# LiFePO4_Power.net
KiCad netlist of a schematic drawn in EAGLE
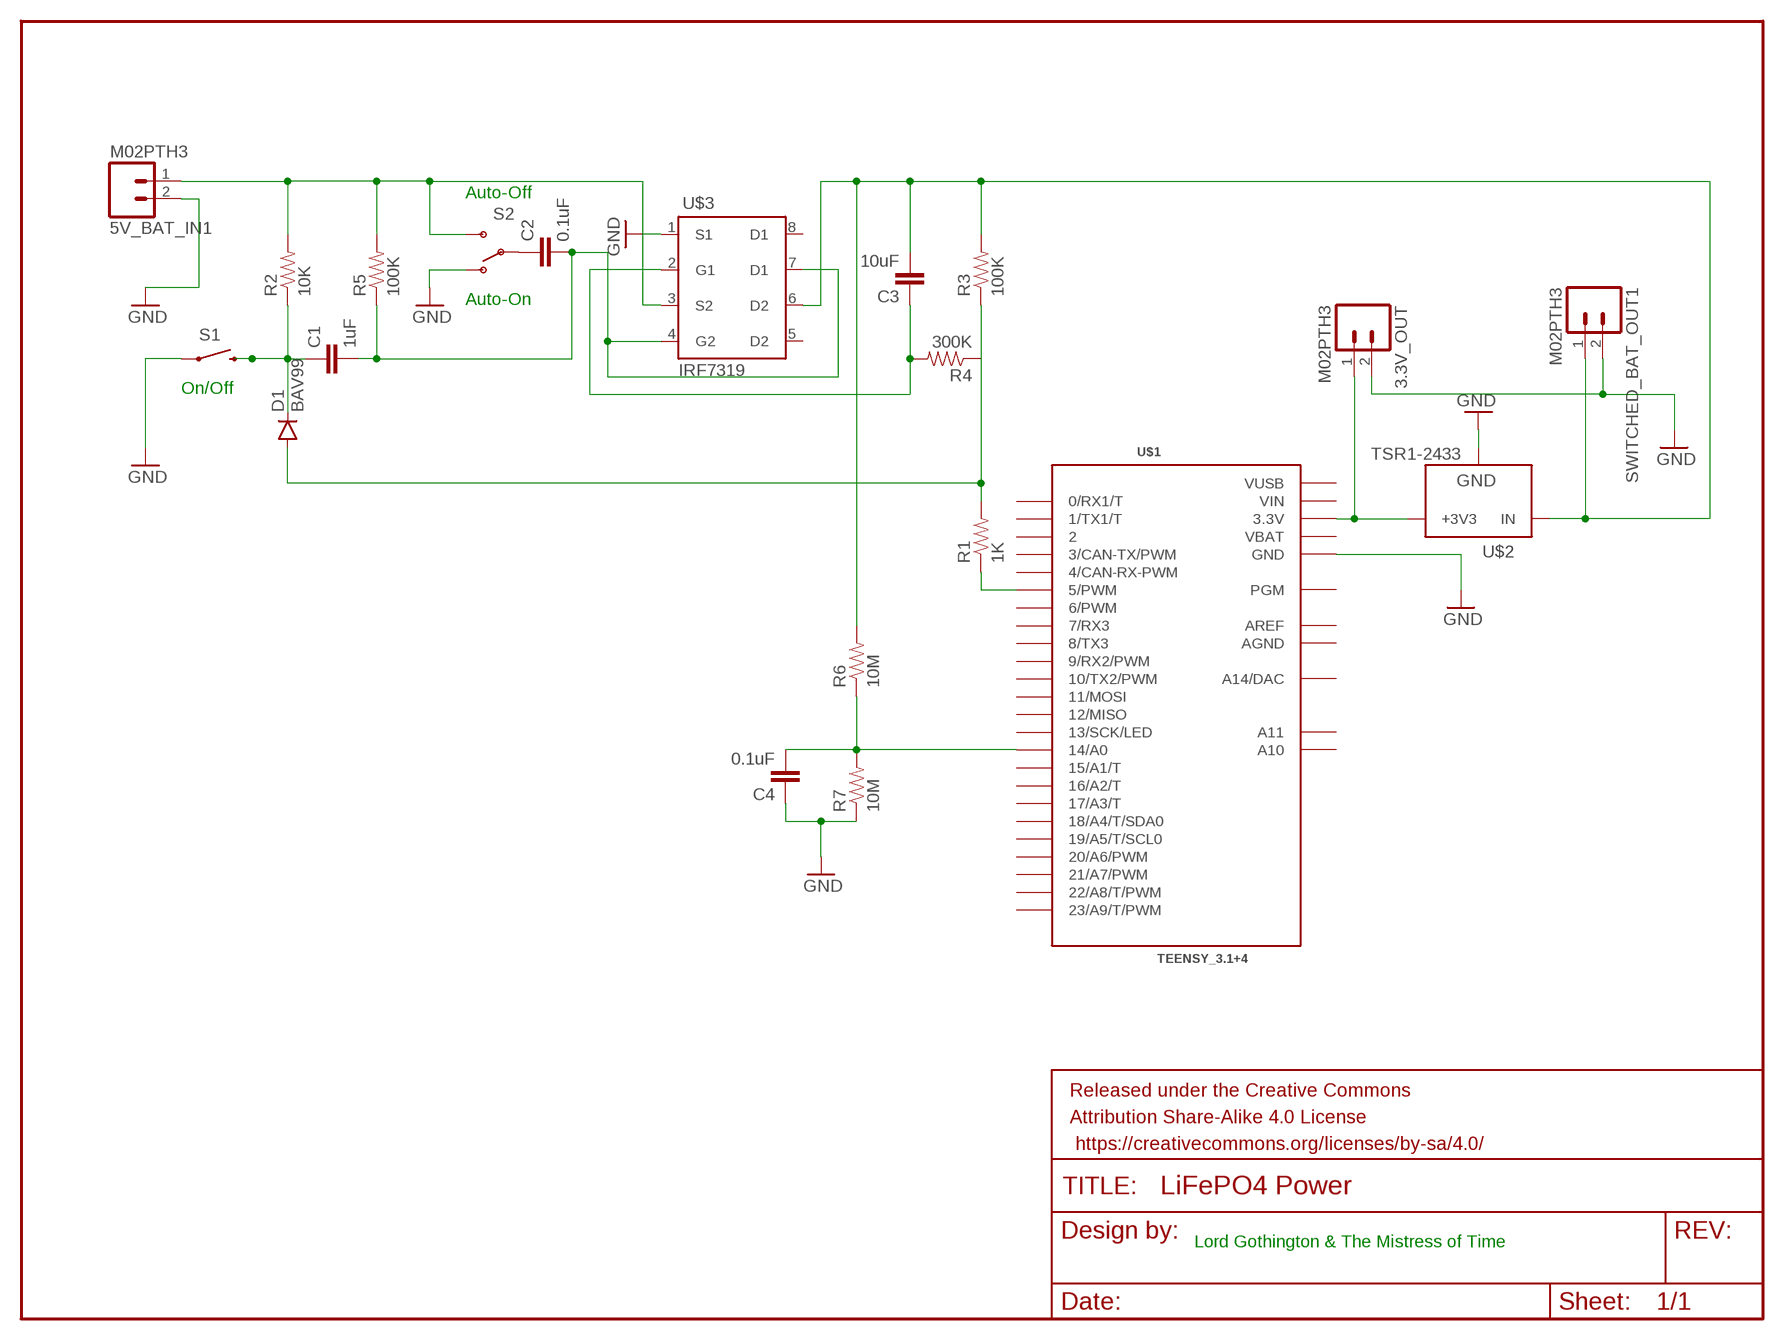
[diagram p0: schematic, sheet 1]

(export (version "E")
  (design (tool "Eeschema 10.0.6"))
  (components
    (comp (ref "3.3V_OUT")
      (value "M02PTH3")
      (footprint "eagle-import:1X02_LONGPADS")
      (libsource (lib "eagle-import") (part "M02PTH3"))
    )
    (comp (ref "5V_BAT_IN1")
      (value "M02PTH3")
      (footprint "eagle-import:1X02_LONGPADS")
      (libsource (lib "eagle-import") (part "M02PTH3"))
    )
    (comp (ref "C1")
      (value "1uF")
      (footprint "eagle-import:0805")
      (libsource (lib "eagle-import") (part "CAP0805"))
    )
    (comp (ref "C2")
      (value "0.1uF")
      (footprint "eagle-import:0805")
      (libsource (lib "eagle-import") (part "CAP0805"))
    )
    (comp (ref "C3")
      (value "10uF")
      (footprint "eagle-import:0805")
      (libsource (lib "eagle-import") (part "CAP0805"))
    )
    (comp (ref "C4")
      (value "0.1uF")
      (footprint "eagle-import:0805")
      (libsource (lib "eagle-import") (part "CAP0805"))
    )
    (comp (ref "D1")
      (value "BAV99")
      (footprint "eagle-import:SMA-DIODE")
      (libsource (lib "eagle-import") (part "DIODESMA"))
    )
    (comp (ref "FRAME1")
      (value "FRAME-LETTER")
      (footprint "eagle-import:CREATIVE_COMMONS")
      (libsource (lib "eagle-import") (part "FRAME-LETTER"))
    )
    (comp (ref "R1")
      (value "1K")
      (footprint "eagle-import:0805")
      (libsource (lib "eagle-import") (part "RESISTOR0805-RES"))
    )
    (comp (ref "R2")
      (value "10K")
      (footprint "eagle-import:0805")
      (libsource (lib "eagle-import") (part "RESISTOR0805-RES"))
    )
    (comp (ref "R3")
      (value "100K")
      (footprint "eagle-import:0805")
      (libsource (lib "eagle-import") (part "RESISTOR0805-RES"))
    )
    (comp (ref "R4")
      (value "300K")
      (footprint "eagle-import:0805")
      (libsource (lib "eagle-import") (part "RESISTOR0805-RES"))
    )
    (comp (ref "R5")
      (value "100K")
      (footprint "eagle-import:0805")
      (libsource (lib "eagle-import") (part "RESISTOR0805-RES"))
    )
    (comp (ref "R6")
      (value "10M")
      (footprint "eagle-import:0805")
      (libsource (lib "eagle-import") (part "RESISTOR0805-RES"))
    )
    (comp (ref "R7")
      (value "10M")
      (footprint "eagle-import:0805")
      (libsource (lib "eagle-import") (part "RESISTOR0805-RES"))
    )
    (comp (ref "S1")
      (value "SWITCH-MOMENTARY-2SMD")
      (footprint "eagle-import:TACTILE-SWITCH-SMD")
      (libsource (lib "eagle-import") (part "SWITCH-MOMENTARY-2SMD"))
    )
    (comp (ref "S2")
      (value "SWITCH-SPDTSMD2")
      (footprint "eagle-import:SWITCH-SPDT-SMD")
      (libsource (lib "eagle-import") (part "SWITCH-SPDTSMD2"))
    )
    (comp (ref "SWITCHED_BAT_OUT1")
      (value "M02PTH3")
      (footprint "eagle-import:1X02_LONGPADS")
      (libsource (lib "eagle-import") (part "M02PTH3"))
    )
    (comp (ref "U$1")
      (value "TEENSY_3.1+4")
      (footprint "eagle-import:TEENSY_3.1+4")
      (libsource (lib "eagle-import") (part "TEENSY_3.1+4"))
    )
    (comp (ref "U$2")
      (value "TSR1-2433")
      (footprint "eagle-import:TSR-1")
      (libsource (lib "eagle-import") (part "TSR1-2433"))
    )
    (comp (ref "U$3")
      (value "IRF7319")
      (footprint "eagle-import:SO08")
      (libsource (lib "eagle-import") (part "IRF7319"))
    )
  )
  (nets
    (net (code "1") (name "/AGND") (class "Default")
      (node (ref "U$1") (pin "AGND") (pinfunction "AGND_AGND") (pintype "power_in"))
    )
    (net (code "2") (name "/AREF") (class "Default")
      (node (ref "U$1") (pin "AREF") (pinfunction "AREF_AREF") (pintype "power_in"))
    )
    (net (code "3") (name "/VBAT") (class "Default")
      (node (ref "U$1") (pin "VBAT") (pinfunction "VBAT_VBAT") (pintype "power_in"))
    )
    (net (code "4") (name "/VIN") (class "Default")
      (node (ref "U$1") (pin "VIN") (pinfunction "VIN_VIN") (pintype "power_in"))
    )
    (net (code "5") (name "/VUSB") (class "Default")
      (node (ref "U$1") (pin "VUSB") (pinfunction "VUSB_VUSB") (pintype "power_in"))
    )
    (net (code "6") (name "GND") (class "Default")
      (node (ref "3.3V_OUT") (pin "2") (pinfunction "2_2") (pintype "passive"))
      (node (ref "5V_BAT_IN1") (pin "2") (pinfunction "2_2") (pintype "passive"))
      (node (ref "C4") (pin "1") (pinfunction "1_1") (pintype "passive"))
      (node (ref "R7") (pin "1") (pinfunction "1_1") (pintype "passive"))
      (node (ref "S1") (pin "1") (pinfunction "1_1") (pintype "passive"))
      (node (ref "S2") (pin "1") (pinfunction "O_1") (pintype "passive"))
      (node (ref "SWITCHED_BAT_OUT1") (pin "2") (pinfunction "2_2") (pintype "passive"))
      (node (ref "U$1") (pin "GND") (pinfunction "GND_GND") (pintype "power_in"))
      (node (ref "U$1") (pin "GND1") (pinfunction "GND_GND1") (pintype "power_in"))
      (node (ref "U$2") (pin "2") (pinfunction "GND_2") (pintype "power_in"))
      (node (ref "U$3") (pin "1") (pinfunction "S1_1") (pintype "bidirectional"))
    )
    (net (code "7") (name "Net-(C4-Pad2)") (class "Default")
      (node (ref "C4") (pin "2") (pinfunction "2_2") (pintype "passive"))
      (node (ref "R6") (pin "1") (pinfunction "1_1") (pintype "passive"))
      (node (ref "R7") (pin "2") (pinfunction "2_2") (pintype "passive"))
      (node (ref "U$1") (pin "14/A0") (pinfunction "14/A0_14/A0") (pintype "bidirectional"))
    )
    (net (code "8") (name "Net-(D1-PadA)") (class "Default")
      (node (ref "D1") (pin "A") (pinfunction "A_A") (pintype "passive"))
      (node (ref "R1") (pin "2") (pinfunction "2_2") (pintype "passive"))
      (node (ref "R3") (pin "1") (pinfunction "1_1") (pintype "passive"))
      (node (ref "R4") (pin "1") (pinfunction "1_1") (pintype "passive"))
    )
    (net (code "9") (name "Net-(S1-2)") (class "Default")
      (node (ref "C1") (pin "1") (pinfunction "1_1") (pintype "passive"))
      (node (ref "D1") (pin "C") (pinfunction "C_C") (pintype "passive"))
      (node (ref "R2") (pin "1") (pinfunction "1_1") (pintype "passive"))
      (node (ref "S1") (pin "3") (pinfunction "2_3") (pintype "passive"))
    )
    (net (code "10") (name "Net-(S2-P)") (class "Default")
      (node (ref "C2") (pin "1") (pinfunction "1_1") (pintype "passive"))
      (node (ref "S2") (pin "2") (pinfunction "P_2") (pintype "passive"))
    )
    (net (code "11") (name "Net-(S2-S)") (class "Default")
      (node (ref "5V_BAT_IN1") (pin "1") (pinfunction "1_1") (pintype "passive"))
      (node (ref "R2") (pin "2") (pinfunction "2_2") (pintype "passive"))
      (node (ref "R5") (pin "2") (pinfunction "2_2") (pintype "passive"))
      (node (ref "S2") (pin "3") (pinfunction "S_3") (pintype "passive"))
      (node (ref "U$3") (pin "3") (pinfunction "S2_3") (pintype "bidirectional"))
    )
    (net (code "12") (name "Net-(U$1-5{slash}PWM)") (class "Default")
      (node (ref "R1") (pin "1") (pinfunction "1_1") (pintype "passive"))
      (node (ref "U$1") (pin "5") (pinfunction "5/PWM_5") (pintype "bidirectional"))
    )
    (net (code "13") (name "Net-(U$2-+3V3)") (class "Default")
      (node (ref "3.3V_OUT") (pin "1") (pinfunction "1_1") (pintype "passive"))
      (node (ref "U$1") (pin "3.3V") (pinfunction "3.3V_3.3V") (pintype "power_in"))
      (node (ref "U$1") (pin "3.3V1") (pinfunction "3.3V_3.3V1") (pintype "power_in"))
      (node (ref "U$2") (pin "3") (pinfunction "+3V3_3") (pintype "power_in"))
    )
    (net (code "14") (name "Net-(U$2-IN)") (class "Default")
      (node (ref "C3") (pin "2") (pinfunction "2_2") (pintype "passive"))
      (node (ref "R3") (pin "2") (pinfunction "2_2") (pintype "passive"))
      (node (ref "R6") (pin "2") (pinfunction "2_2") (pintype "passive"))
      (node (ref "SWITCHED_BAT_OUT1") (pin "1") (pinfunction "1_1") (pintype "passive"))
      (node (ref "U$2") (pin "1") (pinfunction "IN_1") (pintype "power_in"))
      (node (ref "U$3") (pin "6") (pinfunction "D2_6") (pintype "bidirectional"))
    )
    (net (code "15") (name "Net-(U$3-G1)") (class "Default")
      (node (ref "C3") (pin "1") (pinfunction "1_1") (pintype "passive"))
      (node (ref "R4") (pin "2") (pinfunction "2_2") (pintype "passive"))
      (node (ref "U$3") (pin "2") (pinfunction "G1_2") (pintype "bidirectional"))
    )
    (net (code "16") (name "Net-(U$3-G2)") (class "Default")
      (node (ref "C1") (pin "2") (pinfunction "2_2") (pintype "passive"))
      (node (ref "C2") (pin "2") (pinfunction "2_2") (pintype "passive"))
      (node (ref "R5") (pin "1") (pinfunction "1_1") (pintype "passive"))
      (node (ref "U$3") (pin "4") (pinfunction "G2_4") (pintype "bidirectional"))
      (node (ref "U$3") (pin "7") (pinfunction "D1_7") (pintype "bidirectional"))
    )
    (net (code "17") (name "unconnected-(U$1-0{slash}RX1{slash}T-Pad0)") (class "Default")
      (node (ref "U$1") (pin "0") (pinfunction "0/RX1/T_0") (pintype "bidirectional"))
    )
    (net (code "18") (name "unconnected-(U$1-1{slash}TX1{slash}T-Pad1)") (class "Default")
      (node (ref "U$1") (pin "1") (pinfunction "1/TX1/T_1") (pintype "bidirectional"))
    )
    (net (code "19") (name "unconnected-(U$1-3{slash}CAN-TX{slash}PWM-Pad3)") (class "Default")
      (node (ref "U$1") (pin "3") (pinfunction "3/CAN-TX/PWM_3") (pintype "bidirectional"))
    )
    (net (code "20") (name "unconnected-(U$1-4{slash}CAN-RX-PWM-Pad4)") (class "Default")
      (node (ref "U$1") (pin "4") (pinfunction "4/CAN-RX-PWM_4") (pintype "bidirectional"))
    )
    (net (code "21") (name "unconnected-(U$1-6{slash}PWM-Pad6)") (class "Default")
      (node (ref "U$1") (pin "6") (pinfunction "6/PWM_6") (pintype "bidirectional"))
    )
    (net (code "22") (name "unconnected-(U$1-7{slash}RX3-Pad7)") (class "Default")
      (node (ref "U$1") (pin "7") (pinfunction "7/RX3_7") (pintype "bidirectional"))
    )
    (net (code "23") (name "unconnected-(U$1-8{slash}TX3-Pad8)") (class "Default")
      (node (ref "U$1") (pin "8") (pinfunction "8/TX3_8") (pintype "bidirectional"))
    )
    (net (code "24") (name "unconnected-(U$1-9{slash}RX2{slash}PWM-Pad9)") (class "Default")
      (node (ref "U$1") (pin "9") (pinfunction "9/RX2/PWM_9") (pintype "bidirectional"))
    )
    (net (code "25") (name "unconnected-(U$1-10{slash}TX2{slash}PWM-Pad10)") (class "Default")
      (node (ref "U$1") (pin "10") (pinfunction "10/TX2/PWM_10") (pintype "bidirectional"))
    )
    (net (code "26") (name "unconnected-(U$1-11{slash}MOSI-Pad11)") (class "Default")
      (node (ref "U$1") (pin "11") (pinfunction "11/MOSI_11") (pintype "bidirectional"))
    )
    (net (code "27") (name "unconnected-(U$1-12{slash}MISO-Pad12)") (class "Default")
      (node (ref "U$1") (pin "12") (pinfunction "12/MISO_12") (pintype "bidirectional"))
    )
    (net (code "28") (name "unconnected-(U$1-13{slash}SCK{slash}LED-Pad13)") (class "Default")
      (node (ref "U$1") (pin "13") (pinfunction "13/SCK/LED_13") (pintype "bidirectional"))
    )
    (net (code "29") (name "unconnected-(U$1-15{slash}A1{slash}T-Pad15{slash}A1)") (class "Default")
      (node (ref "U$1") (pin "15/A1") (pinfunction "15/A1/T_15/A1") (pintype "bidirectional"))
    )
    (net (code "30") (name "unconnected-(U$1-16{slash}A2{slash}T-Pad16{slash}A2)") (class "Default")
      (node (ref "U$1") (pin "16/A2") (pinfunction "16/A2/T_16/A2") (pintype "bidirectional"))
    )
    (net (code "31") (name "unconnected-(U$1-17{slash}A3{slash}T-Pad17{slash}A3)") (class "Default")
      (node (ref "U$1") (pin "17/A3") (pinfunction "17/A3/T_17/A3") (pintype "bidirectional"))
    )
    (net (code "32") (name "unconnected-(U$1-18{slash}A4{slash}T{slash}SDA0-Pad18{slash}A4)") (class "Default")
      (node (ref "U$1") (pin "18/A4") (pinfunction "18/A4/T/SDA0_18/A4") (pintype "bidirectional"))
    )
    (net (code "33") (name "unconnected-(U$1-19{slash}A5{slash}T{slash}SCL0-Pad19{slash}A5)") (class "Default")
      (node (ref "U$1") (pin "19/A5") (pinfunction "19/A5/T/SCL0_19/A5") (pintype "bidirectional"))
    )
    (net (code "34") (name "unconnected-(U$1-20{slash}A6{slash}PWM-Pad20{slash}A6)") (class "Default")
      (node (ref "U$1") (pin "20/A6") (pinfunction "20/A6/PWM_20/A6") (pintype "bidirectional"))
    )
    (net (code "35") (name "unconnected-(U$1-21{slash}A7{slash}PWM-Pad21{slash}A7)") (class "Default")
      (node (ref "U$1") (pin "21/A7") (pinfunction "21/A7/PWM_21/A7") (pintype "bidirectional"))
    )
    (net (code "36") (name "unconnected-(U$1-22{slash}A8{slash}T{slash}PWM-Pad22{slash}A8)") (class "Default")
      (node (ref "U$1") (pin "22/A8") (pinfunction "22/A8/T/PWM_22/A8") (pintype "bidirectional"))
    )
    (net (code "37") (name "unconnected-(U$1-23{slash}A9{slash}T{slash}PWM-Pad23{slash}A9)") (class "Default")
      (node (ref "U$1") (pin "23/A9") (pinfunction "23/A9/T/PWM_23/A9") (pintype "bidirectional"))
    )
    (net (code "38") (name "unconnected-(U$1-A14{slash}DAC-PadA14)") (class "Default")
      (node (ref "U$1") (pin "A14") (pinfunction "A14/DAC_A14") (pintype "bidirectional"))
    )
    (net (code "39") (name "unconnected-(U$1-Pad2)") (class "Default")
      (node (ref "U$1") (pin "2") (pinfunction "2_2") (pintype "bidirectional"))
    )
    (net (code "40") (name "unconnected-(U$1-PadA10)") (class "Default")
      (node (ref "U$1") (pin "A10") (pinfunction "A10_A10") (pintype "bidirectional"))
    )
    (net (code "41") (name "unconnected-(U$1-PadA11)") (class "Default")
      (node (ref "U$1") (pin "A11") (pinfunction "A11_A11") (pintype "bidirectional"))
    )
    (net (code "42") (name "unconnected-(U$1-PadPGM)") (class "Default")
      (node (ref "U$1") (pin "PGM") (pinfunction "PGM_PGM") (pintype "bidirectional"))
    )
    (net (code "43") (name "unconnected-(U$3-D1-Pad8)") (class "Default")
      (node (ref "U$3") (pin "8") (pinfunction "D1_8") (pintype "bidirectional"))
    )
    (net (code "44") (name "unconnected-(U$3-D2-Pad5)") (class "Default")
      (node (ref "U$3") (pin "5") (pinfunction "D2_5") (pintype "bidirectional"))
    )
  )
)
